# TeensyAmp_R4_1.net
KiCad netlist of a schematic drawn in EAGLE
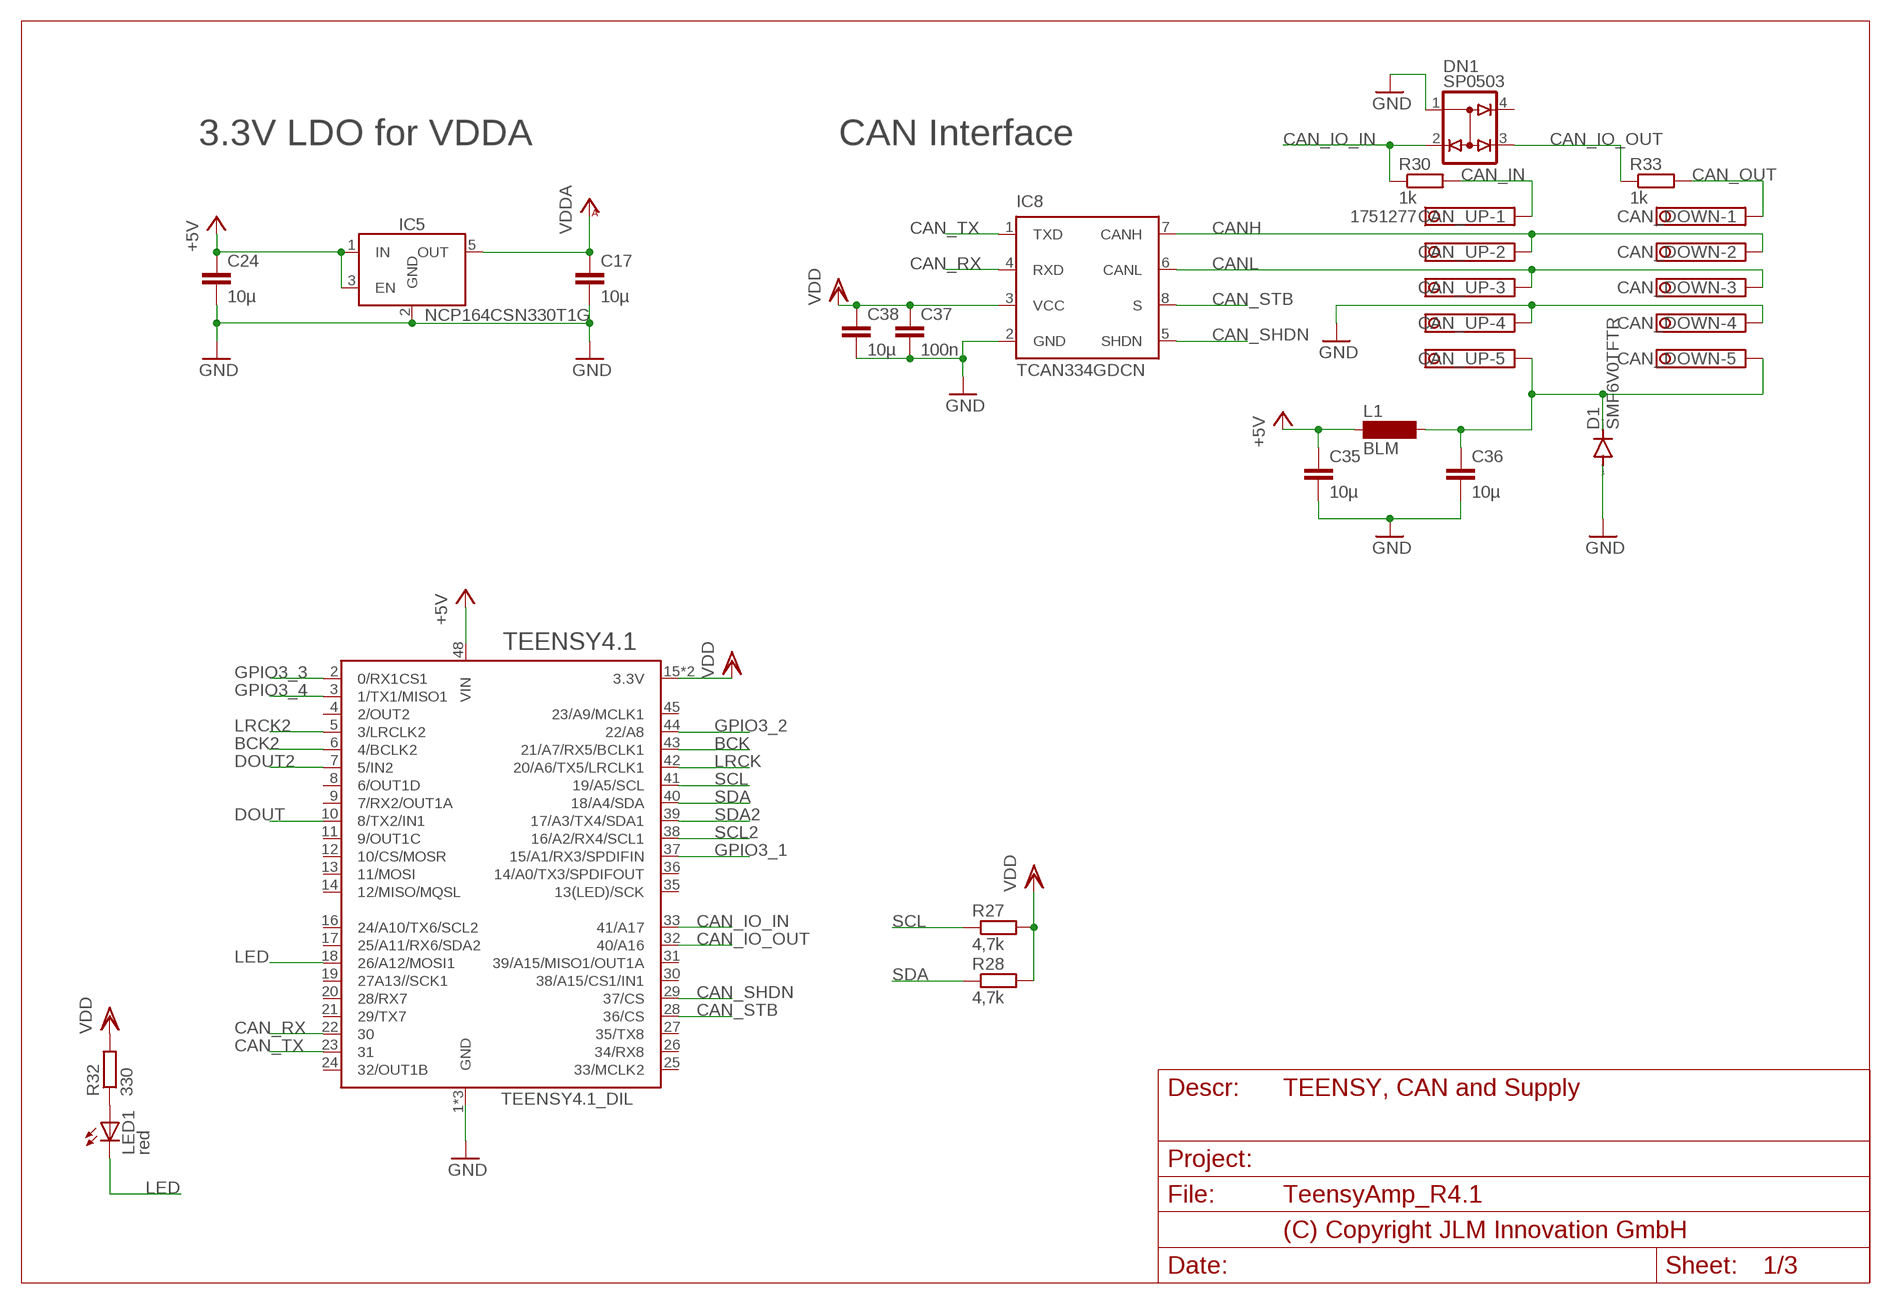
[diagram p0: schematic, sheet 1]
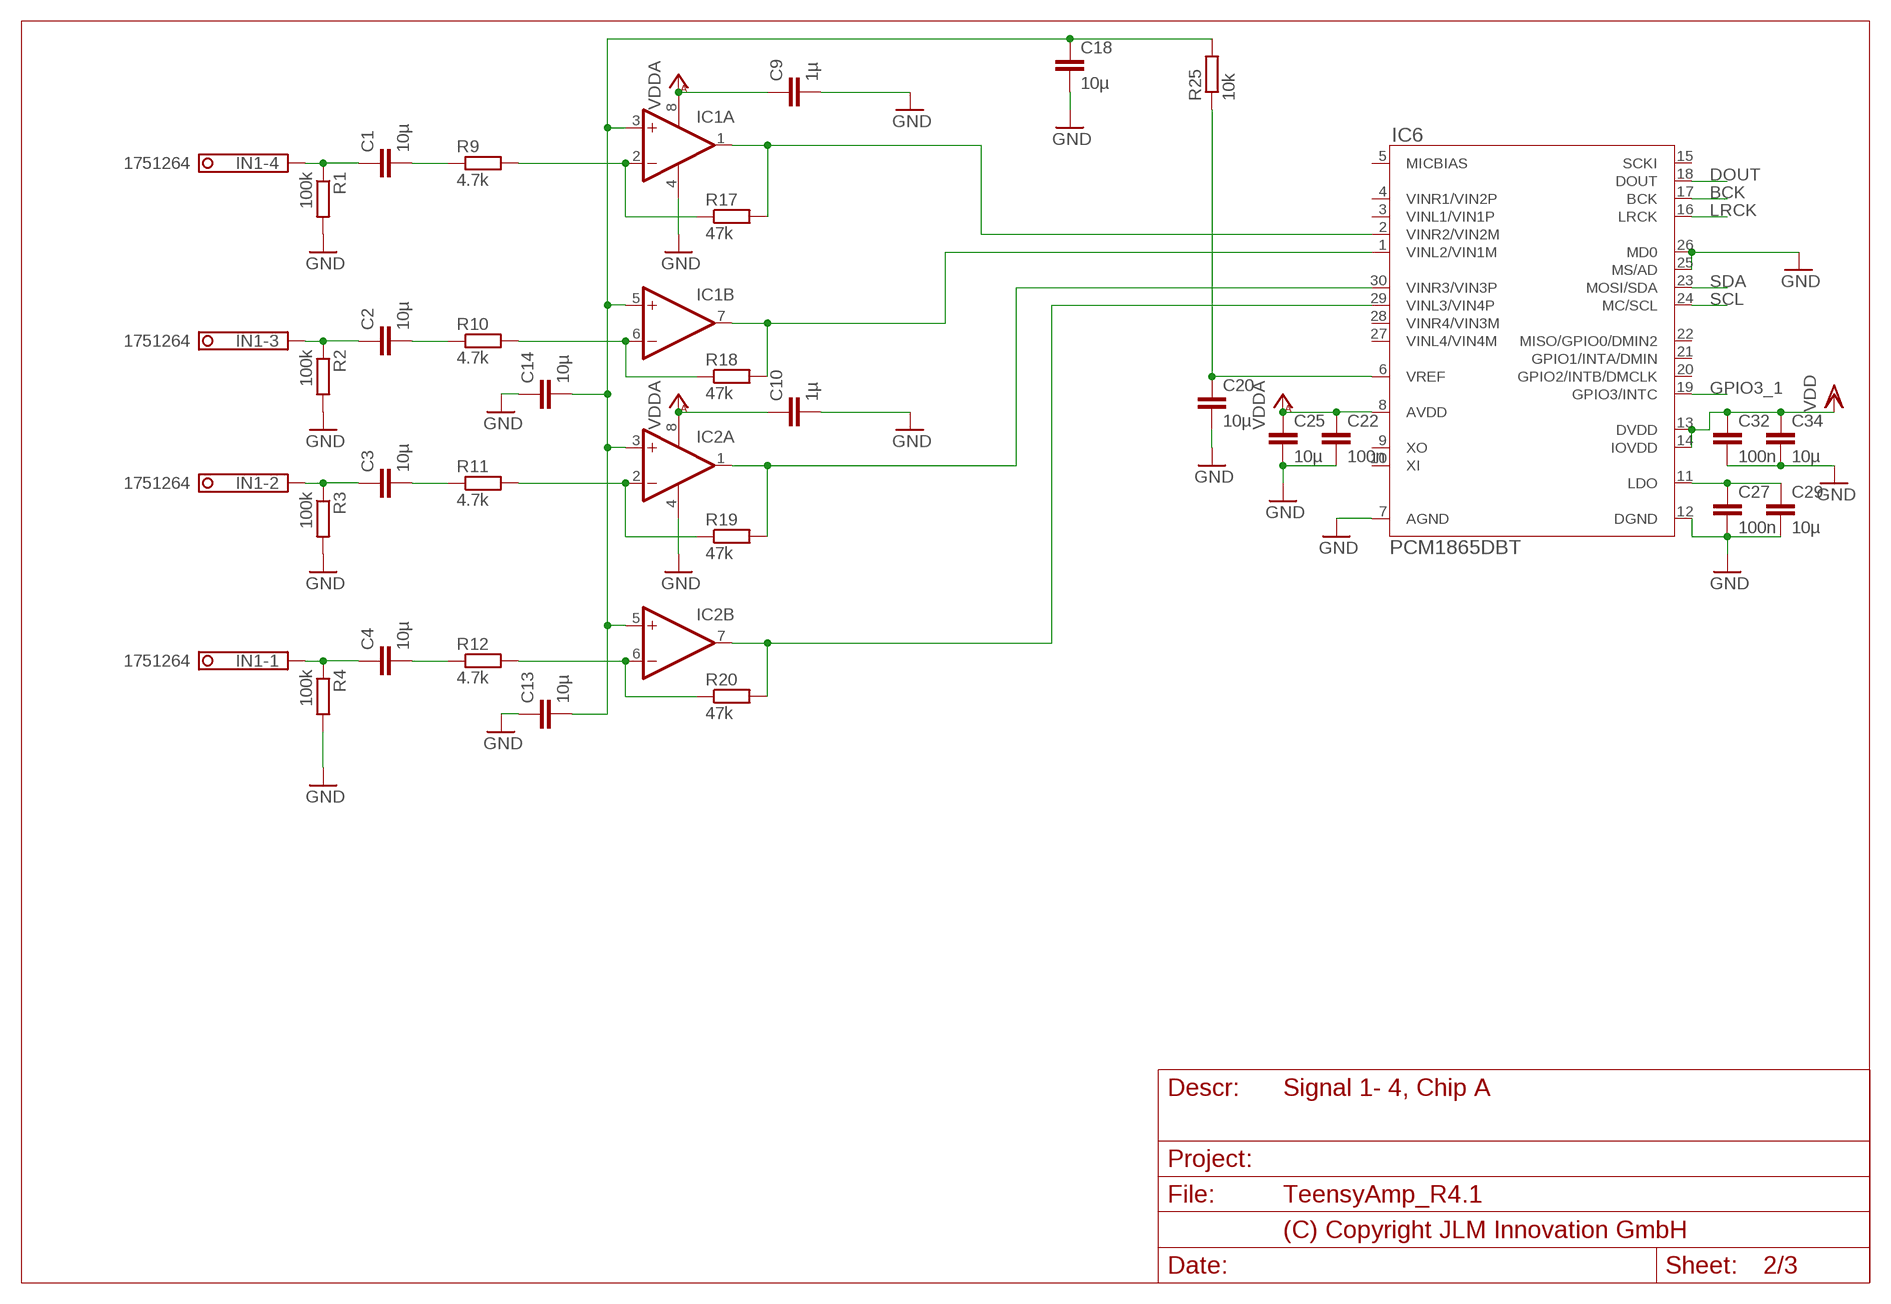
[diagram p1: schematic, sheet 2]
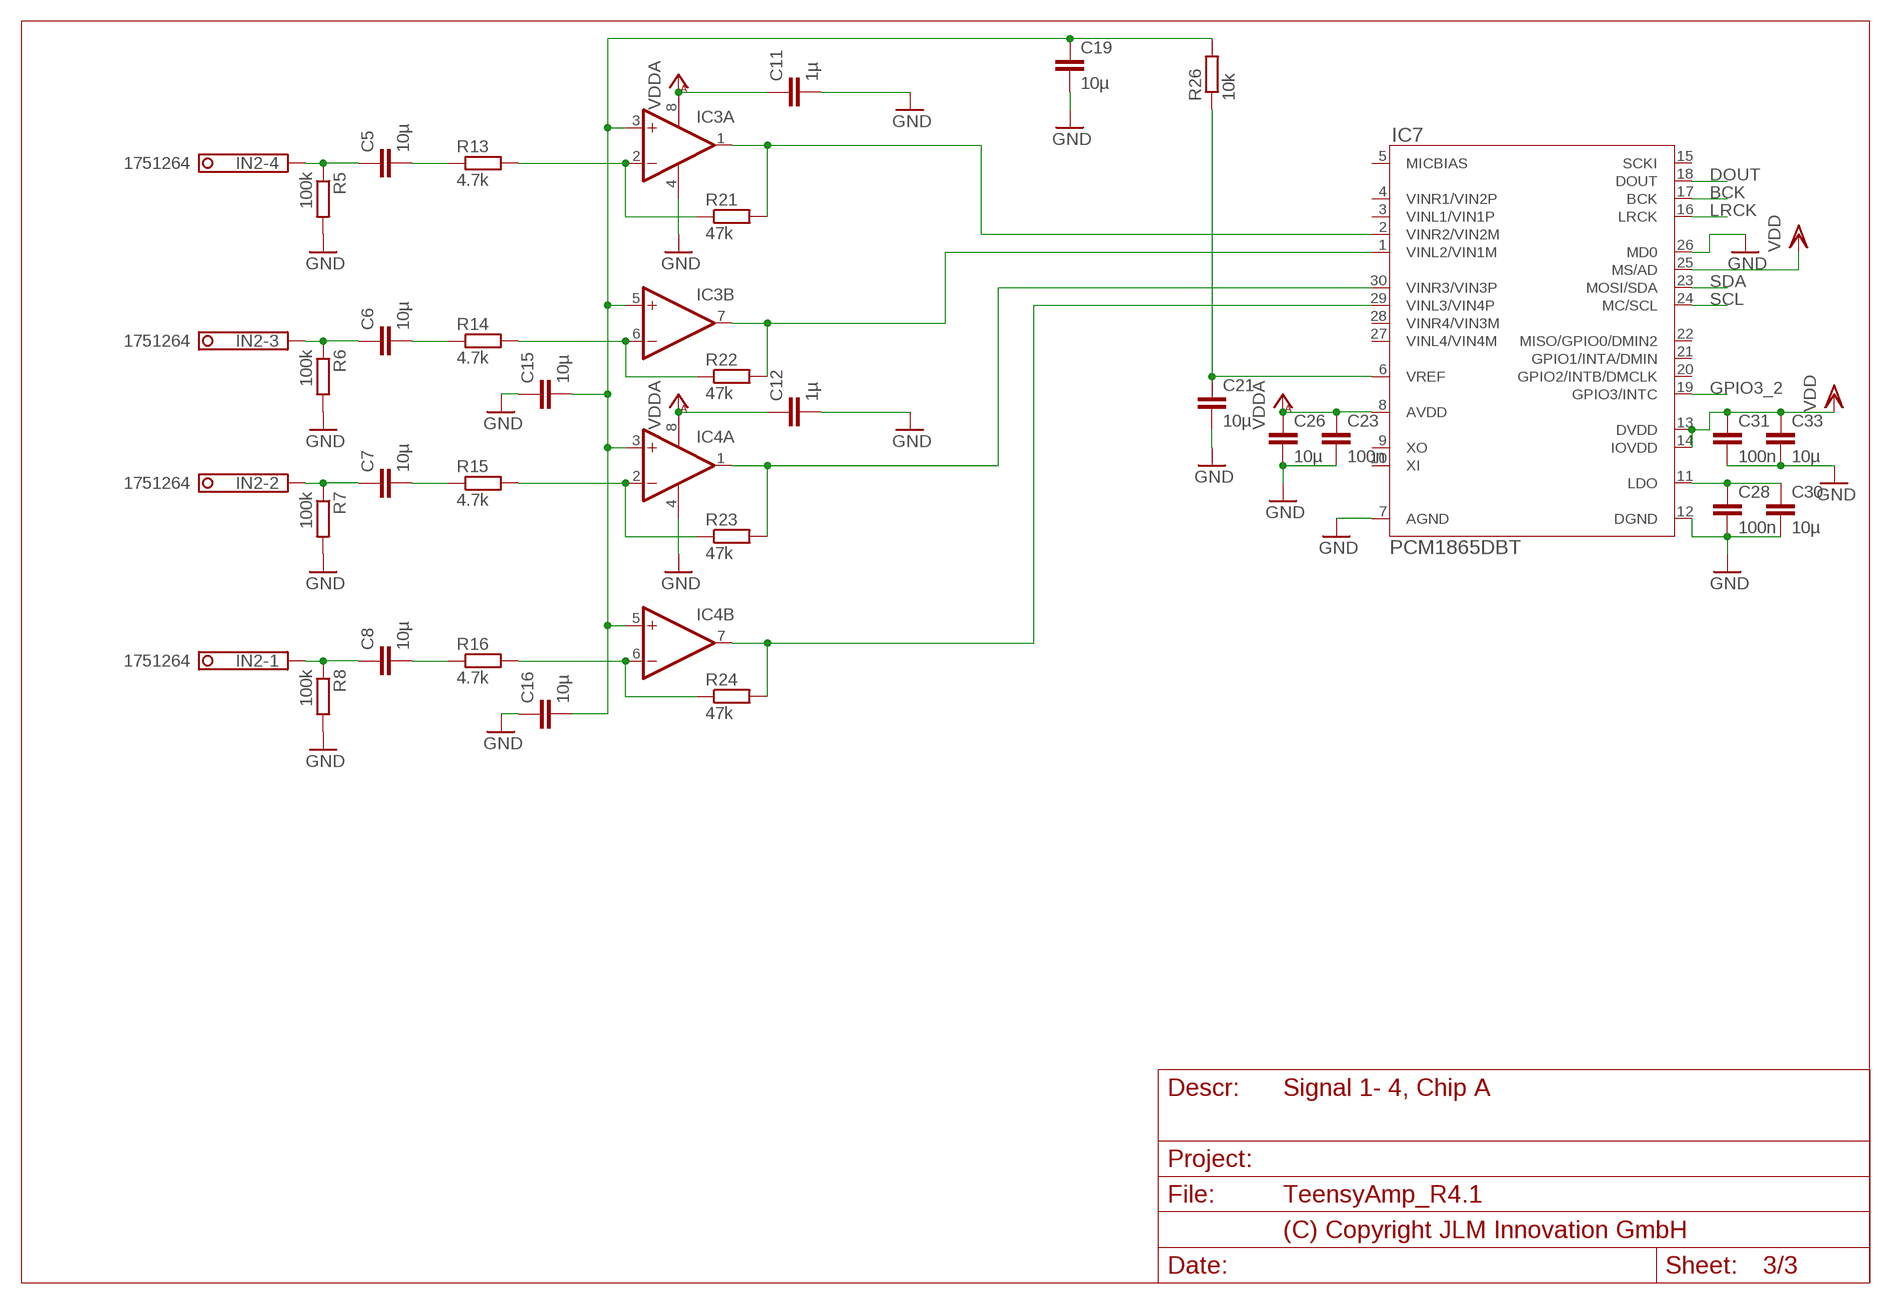
[diagram p2: schematic, sheet 3]

(export (version "E")
  (design (tool "Eeschema 10.0.6"))
  (components
    (comp (ref "C1")
      (value "10µ")
      (footprint "eagle-import:C0805")
      (libsource (lib "eagle-import") (part "C-EUC0805"))
    )
    (comp (ref "C2")
      (value "10µ")
      (footprint "eagle-import:C0805")
      (libsource (lib "eagle-import") (part "C-EUC0805"))
    )
    (comp (ref "C3")
      (value "10µ")
      (footprint "eagle-import:C0805")
      (libsource (lib "eagle-import") (part "C-EUC0805"))
    )
    (comp (ref "C4")
      (value "10µ")
      (footprint "eagle-import:C0805")
      (libsource (lib "eagle-import") (part "C-EUC0805"))
    )
    (comp (ref "C9")
      (value "1µ")
      (footprint "eagle-import:C0603")
      (libsource (lib "eagle-import") (part "C-EUC0603"))
    )
    (comp (ref "C10")
      (value "1µ")
      (footprint "eagle-import:C0603")
      (libsource (lib "eagle-import") (part "C-EUC0603"))
    )
    (comp (ref "C13")
      (value "10µ")
      (footprint "eagle-import:C0603")
      (libsource (lib "eagle-import") (part "C-EUC0603"))
    )
    (comp (ref "C14")
      (value "10µ")
      (footprint "eagle-import:C0603")
      (libsource (lib "eagle-import") (part "C-EUC0603"))
    )
    (comp (ref "C18")
      (value "10µ")
      (footprint "eagle-import:C0603")
      (libsource (lib "eagle-import") (part "C-EUC0603"))
    )
    (comp (ref "C20")
      (value "10µ")
      (footprint "eagle-import:C0603")
      (libsource (lib "eagle-import") (part "C-EUC0603"))
    )
    (comp (ref "C22")
      (value "100n")
      (footprint "eagle-import:C0603")
      (libsource (lib "eagle-import") (part "C-EUC0603"))
    )
    (comp (ref "C25")
      (value "10µ")
      (footprint "eagle-import:C0603")
      (libsource (lib "eagle-import") (part "C-EUC0603"))
    )
    (comp (ref "C27")
      (value "100n")
      (footprint "eagle-import:C0603")
      (libsource (lib "eagle-import") (part "C-EUC0603"))
    )
    (comp (ref "C29")
      (value "10µ")
      (footprint "eagle-import:C0603")
      (libsource (lib "eagle-import") (part "C-EUC0603"))
    )
    (comp (ref "C32")
      (value "100n")
      (footprint "eagle-import:C0603")
      (libsource (lib "eagle-import") (part "C-EUC0603"))
    )
    (comp (ref "C34")
      (value "10µ")
      (footprint "eagle-import:C0603")
      (libsource (lib "eagle-import") (part "C-EUC0603"))
    )
    (comp (ref "IC1")
      (value "OPA2344E")
      (footprint "eagle-import:MSOP08")
      (libsource (lib "eagle-import") (part "OPA2E344"))
    )
    (comp (ref "IC2")
      (value "OPA2344E")
      (footprint "eagle-import:MSOP08")
      (libsource (lib "eagle-import") (part "OPA2E344"))
    )
    (comp (ref "IC6")
      (value "PCM1865DBT")
      (footprint "eagle-import:SOP50P640X120-30N")
      (libsource (lib "eagle-import") (part "PCM1865DBT"))
    )
    (comp (ref "IN1")
      (value "1751264")
      (footprint "eagle-import:1751264")
      (fields (field (name "OC_FARNELL") "2478588"))
      (libsource (lib "eagle-import") (part "1751264"))
    )
    (comp (ref "R1")
      (value "100k")
      (footprint "eagle-import:R0603")
      (libsource (lib "eagle-import") (part "R_JLMR0603"))
    )
    (comp (ref "R2")
      (value "100k")
      (footprint "eagle-import:R0603")
      (libsource (lib "eagle-import") (part "R_JLMR0603"))
    )
    (comp (ref "R3")
      (value "100k")
      (footprint "eagle-import:R0603")
      (libsource (lib "eagle-import") (part "R_JLMR0603"))
    )
    (comp (ref "R4")
      (value "100k")
      (footprint "eagle-import:R0603")
      (libsource (lib "eagle-import") (part "R_JLMR0603"))
    )
    (comp (ref "R9")
      (value "4.7k")
      (footprint "eagle-import:R0603")
      (libsource (lib "eagle-import") (part "R_JLMR0603"))
    )
    (comp (ref "R10")
      (value "4.7k")
      (footprint "eagle-import:R0603")
      (libsource (lib "eagle-import") (part "R_JLMR0603"))
    )
    (comp (ref "R11")
      (value "4.7k")
      (footprint "eagle-import:R0603")
      (libsource (lib "eagle-import") (part "R_JLMR0603"))
    )
    (comp (ref "R12")
      (value "4.7k")
      (footprint "eagle-import:R0603")
      (libsource (lib "eagle-import") (part "R_JLMR0603"))
    )
    (comp (ref "R17")
      (value "47k")
      (footprint "eagle-import:R0603")
      (libsource (lib "eagle-import") (part "R_JLMR0603"))
    )
    (comp (ref "R18")
      (value "47k")
      (footprint "eagle-import:R0603")
      (libsource (lib "eagle-import") (part "R_JLMR0603"))
    )
    (comp (ref "R19")
      (value "47k")
      (footprint "eagle-import:R0603")
      (libsource (lib "eagle-import") (part "R_JLMR0603"))
    )
    (comp (ref "R20")
      (value "47k")
      (footprint "eagle-import:R0603")
      (libsource (lib "eagle-import") (part "R_JLMR0603"))
    )
    (comp (ref "R25")
      (value "10k")
      (footprint "eagle-import:R0603")
      (libsource (lib "eagle-import") (part "R_JLMR0603"))
    )
    (comp (ref "C17")
      (value "10µ")
      (footprint "eagle-import:C0603")
      (libsource (lib "eagle-import") (part "C-EUC0603"))
    )
    (comp (ref "C24")
      (value "10µ")
      (footprint "eagle-import:C0603")
      (libsource (lib "eagle-import") (part "C-EUC0603"))
    )
    (comp (ref "C35")
      (value "10µ")
      (footprint "eagle-import:C0805")
      (libsource (lib "eagle-import") (part "C-EUC0805"))
    )
    (comp (ref "C36")
      (value "10µ")
      (footprint "eagle-import:C0805")
      (libsource (lib "eagle-import") (part "C-EUC0805"))
    )
    (comp (ref "C37")
      (value "100n")
      (footprint "eagle-import:C0603")
      (libsource (lib "eagle-import") (part "C-EUC0603"))
    )
    (comp (ref "C38")
      (value "10µ")
      (footprint "eagle-import:C0603")
      (libsource (lib "eagle-import") (part "C-EUC0603"))
    )
    (comp (ref "CAN_DOWN")
      (value "1751277")
      (footprint "eagle-import:1751277")
      (fields (field (name "OC_RS") "8024855"))
      (libsource (lib "eagle-import") (part "1751277"))
    )
    (comp (ref "CAN_UP")
      (value "1751277")
      (footprint "eagle-import:1751277")
      (fields (field (name "OC_RS") "8024855"))
      (libsource (lib "eagle-import") (part "1751277"))
    )
    (comp (ref "D1")
      (value "SMF6V0TFTR")
      (footprint "eagle-import:SOD123")
      (libsource (lib "eagle-import") (part "DIODE-SOD123"))
    )
    (comp (ref "DN1")
      (value "SP0503")
      (footprint "eagle-import:SOT143-R")
      (fields (field (name "OC_FARNELL") "1827633"))
      (libsource (lib "eagle-import") (part "SP0503"))
    )
    (comp (ref "IC5")
      (value "NCP164CSN330T1G")
      (footprint "eagle-import:SOT23-5")
      (libsource (lib "eagle-import") (part "LDO_ENSOT23-5"))
    )
    (comp (ref "IC8")
      (value "TCAN334GDCN")
      (footprint "eagle-import:SOT65P280X145-8N")
      (libsource (lib "eagle-import") (part "TCAN330DCN"))
    )
    (comp (ref "L1")
      (value "BLM")
      (footprint "eagle-import:R0805")
      (libsource (lib "eagle-import") (part "L_JLM0805"))
    )
    (comp (ref "LED1")
      (value "red")
      (footprint "eagle-import:LED5MM")
      (libsource (lib "eagle-import") (part "LED5MM"))
    )
    (comp (ref "R27")
      (value "4,7k")
      (footprint "eagle-import:R0603")
      (libsource (lib "eagle-import") (part "R_JLMR0603"))
    )
    (comp (ref "R28")
      (value "4,7k")
      (footprint "eagle-import:R0603")
      (libsource (lib "eagle-import") (part "R_JLMR0603"))
    )
    (comp (ref "R30")
      (value "1k")
      (footprint "eagle-import:R0603")
      (libsource (lib "eagle-import") (part "R_JLMR0603"))
    )
    (comp (ref "R32")
      (value "330")
      (footprint "eagle-import:R0603")
      (libsource (lib "eagle-import") (part "R_JLMR0603"))
    )
    (comp (ref "R33")
      (value "1k")
      (footprint "eagle-import:R0603")
      (libsource (lib "eagle-import") (part "R_JLMR0603"))
    )
    (comp (ref "TEENSY4.1")
      (value "TEENSY4.1_DIL")
      (footprint "eagle-import:TEENSY4.1_DIL")
      (libsource (lib "eagle-import") (part "TEENSY4.1_DIL"))
    )
    (comp (ref "C5")
      (value "10µ")
      (footprint "eagle-import:C0805")
      (libsource (lib "eagle-import") (part "C-EUC0805"))
    )
    (comp (ref "C6")
      (value "10µ")
      (footprint "eagle-import:C0805")
      (libsource (lib "eagle-import") (part "C-EUC0805"))
    )
    (comp (ref "C7")
      (value "10µ")
      (footprint "eagle-import:C0805")
      (libsource (lib "eagle-import") (part "C-EUC0805"))
    )
    (comp (ref "C8")
      (value "10µ")
      (footprint "eagle-import:C0805")
      (libsource (lib "eagle-import") (part "C-EUC0805"))
    )
    (comp (ref "C11")
      (value "1µ")
      (footprint "eagle-import:C0603")
      (libsource (lib "eagle-import") (part "C-EUC0603"))
    )
    (comp (ref "C12")
      (value "1µ")
      (footprint "eagle-import:C0603")
      (libsource (lib "eagle-import") (part "C-EUC0603"))
    )
    (comp (ref "C15")
      (value "10µ")
      (footprint "eagle-import:C0603")
      (libsource (lib "eagle-import") (part "C-EUC0603"))
    )
    (comp (ref "C16")
      (value "10µ")
      (footprint "eagle-import:C0603")
      (libsource (lib "eagle-import") (part "C-EUC0603"))
    )
    (comp (ref "C19")
      (value "10µ")
      (footprint "eagle-import:C0603")
      (libsource (lib "eagle-import") (part "C-EUC0603"))
    )
    (comp (ref "C21")
      (value "10µ")
      (footprint "eagle-import:C0603")
      (libsource (lib "eagle-import") (part "C-EUC0603"))
    )
    (comp (ref "C23")
      (value "100n")
      (footprint "eagle-import:C0603")
      (libsource (lib "eagle-import") (part "C-EUC0603"))
    )
    (comp (ref "C26")
      (value "10µ")
      (footprint "eagle-import:C0603")
      (libsource (lib "eagle-import") (part "C-EUC0603"))
    )
    (comp (ref "C28")
      (value "100n")
      (footprint "eagle-import:C0603")
      (libsource (lib "eagle-import") (part "C-EUC0603"))
    )
    (comp (ref "C30")
      (value "10µ")
      (footprint "eagle-import:C0603")
      (libsource (lib "eagle-import") (part "C-EUC0603"))
    )
    (comp (ref "C31")
      (value "100n")
      (footprint "eagle-import:C0603")
      (libsource (lib "eagle-import") (part "C-EUC0603"))
    )
    (comp (ref "C33")
      (value "10µ")
      (footprint "eagle-import:C0603")
      (libsource (lib "eagle-import") (part "C-EUC0603"))
    )
    (comp (ref "IC3")
      (value "OPA2344E")
      (footprint "eagle-import:MSOP08")
      (libsource (lib "eagle-import") (part "OPA2E344"))
    )
    (comp (ref "IC4")
      (value "OPA2344E")
      (footprint "eagle-import:MSOP08")
      (libsource (lib "eagle-import") (part "OPA2E344"))
    )
    (comp (ref "IC7")
      (value "PCM1865DBT")
      (footprint "eagle-import:SOP50P640X120-30N")
      (libsource (lib "eagle-import") (part "PCM1865DBT"))
    )
    (comp (ref "IN2")
      (value "1751264")
      (footprint "eagle-import:1751264")
      (fields (field (name "OC_FARNELL") "2478588") (field (name "OC_RS") "8024852"))
      (libsource (lib "eagle-import") (part "1751264"))
    )
    (comp (ref "R5")
      (value "100k")
      (footprint "eagle-import:R0603")
      (libsource (lib "eagle-import") (part "R_JLMR0603"))
    )
    (comp (ref "R6")
      (value "100k")
      (footprint "eagle-import:R0603")
      (libsource (lib "eagle-import") (part "R_JLMR0603"))
    )
    (comp (ref "R7")
      (value "100k")
      (footprint "eagle-import:R0603")
      (libsource (lib "eagle-import") (part "R_JLMR0603"))
    )
    (comp (ref "R8")
      (value "100k")
      (footprint "eagle-import:R0603")
      (libsource (lib "eagle-import") (part "R_JLMR0603"))
    )
    (comp (ref "R13")
      (value "4.7k")
      (footprint "eagle-import:R0603")
      (libsource (lib "eagle-import") (part "R_JLMR0603"))
    )
    (comp (ref "R14")
      (value "4.7k")
      (footprint "eagle-import:R0603")
      (libsource (lib "eagle-import") (part "R_JLMR0603"))
    )
    (comp (ref "R15")
      (value "4.7k")
      (footprint "eagle-import:R0603")
      (libsource (lib "eagle-import") (part "R_JLMR0603"))
    )
    (comp (ref "R16")
      (value "4.7k")
      (footprint "eagle-import:R0603")
      (libsource (lib "eagle-import") (part "R_JLMR0603"))
    )
    (comp (ref "R21")
      (value "47k")
      (footprint "eagle-import:R0603")
      (libsource (lib "eagle-import") (part "R_JLMR0603"))
    )
    (comp (ref "R22")
      (value "47k")
      (footprint "eagle-import:R0603")
      (libsource (lib "eagle-import") (part "R_JLMR0603"))
    )
    (comp (ref "R23")
      (value "47k")
      (footprint "eagle-import:R0603")
      (libsource (lib "eagle-import") (part "R_JLMR0603"))
    )
    (comp (ref "R24")
      (value "47k")
      (footprint "eagle-import:R0603")
      (libsource (lib "eagle-import") (part "R_JLMR0603"))
    )
    (comp (ref "R26")
      (value "10k")
      (footprint "eagle-import:R0603")
      (libsource (lib "eagle-import") (part "R_JLMR0603"))
    )
  )
  (nets
    (net (code "1") (name "+5V") (class "Default")
      (node (ref "C24") (pin "1") (pinfunction "1_1") (pintype "passive"))
      (node (ref "C35") (pin "1") (pinfunction "1_1") (pintype "passive"))
      (node (ref "IC5") (pin "1") (pinfunction "IN_1") (pintype "input"))
      (node (ref "IC5") (pin "3") (pinfunction "EN_3") (pintype "input"))
      (node (ref "L1") (pin "1") (pinfunction "1_1") (pintype "passive"))
      (node (ref "TEENSY4.1") (pin "48") (pinfunction "VIN_48") (pintype "power_in"))
    )
    (net (code "2") (name "BCK") (class "Default")
      (node (ref "IC6") (pin "17") (pinfunction "BCK_17") (pintype "bidirectional"))
      (node (ref "IC7") (pin "17") (pinfunction "BCK_17") (pintype "bidirectional"))
      (node (ref "TEENSY4.1") (pin "43") (pinfunction "21/A7/RX5/BCLK1_43") (pintype "bidirectional"))
    )
    (net (code "3") (name "BCK2") (class "Default")
      (node (ref "TEENSY4.1") (pin "6") (pinfunction "4/BCLK2_6") (pintype "bidirectional"))
    )
    (net (code "4") (name "CANH") (class "Default")
      (node (ref "CAN_DOWN") (pin "2") (pinfunction "K_2") (pintype "passive"))
      (node (ref "CAN_UP") (pin "2") (pinfunction "K_2") (pintype "passive"))
      (node (ref "IC8") (pin "7") (pinfunction "CANH_7") (pintype "passive"))
    )
    (net (code "5") (name "CANL") (class "Default")
      (node (ref "CAN_DOWN") (pin "3") (pinfunction "K_3") (pintype "passive"))
      (node (ref "CAN_UP") (pin "3") (pinfunction "K_3") (pintype "passive"))
      (node (ref "IC8") (pin "6") (pinfunction "CANL_6") (pintype "passive"))
    )
    (net (code "6") (name "CAN_IN") (class "Default")
      (node (ref "CAN_UP") (pin "1") (pinfunction "K_1") (pintype "passive"))
      (node (ref "R30") (pin "2") (pinfunction "2_2") (pintype "passive"))
    )
    (net (code "7") (name "CAN_IO_IN") (class "Default")
      (node (ref "DN1") (pin "2") (pinfunction "C2_2") (pintype "passive"))
      (node (ref "R30") (pin "1") (pinfunction "1_1") (pintype "passive"))
      (node (ref "TEENSY4.1") (pin "33") (pinfunction "41/A17_33") (pintype "bidirectional"))
    )
    (net (code "8") (name "CAN_IO_OUT") (class "Default")
      (node (ref "DN1") (pin "3") (pinfunction "C3_3") (pintype "passive"))
      (node (ref "R33") (pin "1") (pinfunction "1_1") (pintype "passive"))
      (node (ref "TEENSY4.1") (pin "32") (pinfunction "40/A16_32") (pintype "bidirectional"))
    )
    (net (code "9") (name "CAN_OUT") (class "Default")
      (node (ref "CAN_DOWN") (pin "1") (pinfunction "K_1") (pintype "passive"))
      (node (ref "R33") (pin "2") (pinfunction "2_2") (pintype "passive"))
    )
    (net (code "10") (name "CAN_RX") (class "Default")
      (node (ref "IC8") (pin "4") (pinfunction "RXD_4") (pintype "output"))
      (node (ref "TEENSY4.1") (pin "22") (pinfunction "30_22") (pintype "bidirectional"))
    )
    (net (code "11") (name "CAN_SHDN") (class "Default")
      (node (ref "IC8") (pin "5") (pinfunction "SHDN_5") (pintype "input"))
      (node (ref "TEENSY4.1") (pin "29") (pinfunction "37/CS_29") (pintype "bidirectional"))
    )
    (net (code "12") (name "CAN_STB") (class "Default")
      (node (ref "IC8") (pin "8") (pinfunction "S_8") (pintype "input"))
      (node (ref "TEENSY4.1") (pin "28") (pinfunction "36/CS_28") (pintype "bidirectional"))
    )
    (net (code "13") (name "CAN_TX") (class "Default")
      (node (ref "IC8") (pin "1") (pinfunction "TXD_1") (pintype "input"))
      (node (ref "TEENSY4.1") (pin "23") (pinfunction "31_23") (pintype "bidirectional"))
    )
    (net (code "14") (name "DOUT") (class "Default")
      (node (ref "IC6") (pin "18") (pinfunction "DOUT_18") (pintype "output"))
      (node (ref "IC7") (pin "18") (pinfunction "DOUT_18") (pintype "output"))
      (node (ref "TEENSY4.1") (pin "10") (pinfunction "8/TX2/IN1_10") (pintype "bidirectional"))
    )
    (net (code "15") (name "DOUT2") (class "Default")
      (node (ref "TEENSY4.1") (pin "7") (pinfunction "5/IN2_7") (pintype "bidirectional"))
    )
    (net (code "16") (name "GND") (class "Default")
      (node (ref "C10") (pin "2") (pinfunction "2_2") (pintype "passive"))
      (node (ref "C11") (pin "2") (pinfunction "2_2") (pintype "passive"))
      (node (ref "C12") (pin "2") (pinfunction "2_2") (pintype "passive"))
      (node (ref "C13") (pin "1") (pinfunction "1_1") (pintype "passive"))
      (node (ref "C14") (pin "1") (pinfunction "1_1") (pintype "passive"))
      (node (ref "C15") (pin "1") (pinfunction "1_1") (pintype "passive"))
      (node (ref "C16") (pin "1") (pinfunction "1_1") (pintype "passive"))
      (node (ref "C17") (pin "2") (pinfunction "2_2") (pintype "passive"))
      (node (ref "C18") (pin "2") (pinfunction "2_2") (pintype "passive"))
      (node (ref "C19") (pin "2") (pinfunction "2_2") (pintype "passive"))
      (node (ref "C20") (pin "2") (pinfunction "2_2") (pintype "passive"))
      (node (ref "C21") (pin "2") (pinfunction "2_2") (pintype "passive"))
      (node (ref "C22") (pin "2") (pinfunction "2_2") (pintype "passive"))
      (node (ref "C23") (pin "2") (pinfunction "2_2") (pintype "passive"))
      (node (ref "C24") (pin "2") (pinfunction "2_2") (pintype "passive"))
      (node (ref "C25") (pin "2") (pinfunction "2_2") (pintype "passive"))
      (node (ref "C26") (pin "2") (pinfunction "2_2") (pintype "passive"))
      (node (ref "C27") (pin "2") (pinfunction "2_2") (pintype "passive"))
      (node (ref "C28") (pin "2") (pinfunction "2_2") (pintype "passive"))
      (node (ref "C29") (pin "2") (pinfunction "2_2") (pintype "passive"))
      (node (ref "C30") (pin "2") (pinfunction "2_2") (pintype "passive"))
      (node (ref "C31") (pin "2") (pinfunction "2_2") (pintype "passive"))
      (node (ref "C32") (pin "2") (pinfunction "2_2") (pintype "passive"))
      (node (ref "C33") (pin "2") (pinfunction "2_2") (pintype "passive"))
      (node (ref "C34") (pin "2") (pinfunction "2_2") (pintype "passive"))
      (node (ref "C35") (pin "2") (pinfunction "2_2") (pintype "passive"))
      (node (ref "C36") (pin "2") (pinfunction "2_2") (pintype "passive"))
      (node (ref "C37") (pin "2") (pinfunction "2_2") (pintype "passive"))
      (node (ref "C38") (pin "2") (pinfunction "2_2") (pintype "passive"))
      (node (ref "C9") (pin "2") (pinfunction "2_2") (pintype "passive"))
      (node (ref "CAN_DOWN") (pin "4") (pinfunction "K_4") (pintype "passive"))
      (node (ref "CAN_UP") (pin "4") (pinfunction "K_4") (pintype "passive"))
      (node (ref "D1") (pin "A") (pinfunction "A_A") (pintype "passive"))
      (node (ref "DN1") (pin "1") (pinfunction "A1_1") (pintype "passive"))
      (node (ref "IC1") (pin "4") (pinfunction "V-_4") (pintype "power_in"))
      (node (ref "IC2") (pin "4") (pinfunction "V-_4") (pintype "power_in"))
      (node (ref "IC3") (pin "4") (pinfunction "V-_4") (pintype "power_in"))
      (node (ref "IC4") (pin "4") (pinfunction "V-_4") (pintype "power_in"))
      (node (ref "IC5") (pin "2") (pinfunction "GND_2") (pintype "power_in"))
      (node (ref "IC6") (pin "12") (pinfunction "DGND_12") (pintype "power_in"))
      (node (ref "IC6") (pin "25") (pinfunction "MS/AD_25") (pintype "input"))
      (node (ref "IC6") (pin "26") (pinfunction "MD0_26") (pintype "input"))
      (node (ref "IC6") (pin "7") (pinfunction "AGND_7") (pintype "power_in"))
      (node (ref "IC7") (pin "12") (pinfunction "DGND_12") (pintype "power_in"))
      (node (ref "IC7") (pin "26") (pinfunction "MD0_26") (pintype "input"))
      (node (ref "IC7") (pin "7") (pinfunction "AGND_7") (pintype "power_in"))
      (node (ref "IC8") (pin "2") (pinfunction "GND_2") (pintype "power_in"))
      (node (ref "R1") (pin "2") (pinfunction "2_2") (pintype "passive"))
      (node (ref "R2") (pin "2") (pinfunction "2_2") (pintype "passive"))
      (node (ref "R3") (pin "2") (pinfunction "2_2") (pintype "passive"))
      (node (ref "R4") (pin "2") (pinfunction "2_2") (pintype "passive"))
      (node (ref "R5") (pin "2") (pinfunction "2_2") (pintype "passive"))
      (node (ref "R6") (pin "2") (pinfunction "2_2") (pintype "passive"))
      (node (ref "R7") (pin "2") (pinfunction "2_2") (pintype "passive"))
      (node (ref "R8") (pin "2") (pinfunction "2_2") (pintype "passive"))
      (node (ref "TEENSY4.1") (pin "1") (pinfunction "GND_1") (pintype "power_in"))
      (node (ref "TEENSY4.1") (pin "34") (pinfunction "GND_34") (pintype "power_in"))
      (node (ref "TEENSY4.1") (pin "47") (pinfunction "GND_47") (pintype "power_in"))
    )
    (net (code "17") (name "GPIO3_1") (class "Default")
      (node (ref "IC6") (pin "19") (pinfunction "GPIO3/INTC_19") (pintype "bidirectional"))
      (node (ref "TEENSY4.1") (pin "37") (pinfunction "15/A1/RX3/SPDIFIN_37") (pintype "bidirectional"))
    )
    (net (code "18") (name "GPIO3_2") (class "Default")
      (node (ref "IC7") (pin "19") (pinfunction "GPIO3/INTC_19") (pintype "bidirectional"))
      (node (ref "TEENSY4.1") (pin "44") (pinfunction "22/A8_44") (pintype "bidirectional"))
    )
    (net (code "19") (name "GPIO3_3") (class "Default")
      (node (ref "TEENSY4.1") (pin "2") (pinfunction "0/RX1CS1_2") (pintype "bidirectional"))
    )
    (net (code "20") (name "GPIO3_4") (class "Default")
      (node (ref "TEENSY4.1") (pin "3") (pinfunction "1/TX1/MISO1_3") (pintype "bidirectional"))
    )
    (net (code "21") (name "LED") (class "Default")
      (node (ref "LED1") (pin "K") (pinfunction "C_K") (pintype "passive"))
      (node (ref "TEENSY4.1") (pin "18") (pinfunction "26/A12/MOSI1_18") (pintype "bidirectional"))
    )
    (net (code "22") (name "LRCK") (class "Default")
      (node (ref "IC6") (pin "16") (pinfunction "LRCK_16") (pintype "bidirectional"))
      (node (ref "IC7") (pin "16") (pinfunction "LRCK_16") (pintype "bidirectional"))
      (node (ref "TEENSY4.1") (pin "42") (pinfunction "20/A6/TX5/LRCLK1_42") (pintype "bidirectional"))
    )
    (net (code "23") (name "LRCK2") (class "Default")
      (node (ref "TEENSY4.1") (pin "5") (pinfunction "3/LRCLK2_5") (pintype "bidirectional"))
    )
    (net (code "24") (name "Net-(C1-Pad2)") (class "Default")
      (node (ref "C1") (pin "2") (pinfunction "2_2") (pintype "passive"))
      (node (ref "R9") (pin "1") (pinfunction "1_1") (pintype "passive"))
    )
    (net (code "25") (name "Net-(C2-Pad2)") (class "Default")
      (node (ref "C2") (pin "2") (pinfunction "2_2") (pintype "passive"))
      (node (ref "R10") (pin "1") (pinfunction "1_1") (pintype "passive"))
    )
    (net (code "26") (name "Net-(C3-Pad2)") (class "Default")
      (node (ref "C3") (pin "2") (pinfunction "2_2") (pintype "passive"))
      (node (ref "R11") (pin "1") (pinfunction "1_1") (pintype "passive"))
    )
    (net (code "27") (name "Net-(C4-Pad2)") (class "Default")
      (node (ref "C4") (pin "2") (pinfunction "2_2") (pintype "passive"))
      (node (ref "R12") (pin "1") (pinfunction "1_1") (pintype "passive"))
    )
    (net (code "28") (name "Net-(C5-Pad2)") (class "Default")
      (node (ref "C5") (pin "2") (pinfunction "2_2") (pintype "passive"))
      (node (ref "R13") (pin "1") (pinfunction "1_1") (pintype "passive"))
    )
    (net (code "29") (name "Net-(C6-Pad2)") (class "Default")
      (node (ref "C6") (pin "2") (pinfunction "2_2") (pintype "passive"))
      (node (ref "R14") (pin "1") (pinfunction "1_1") (pintype "passive"))
    )
    (net (code "30") (name "Net-(C7-Pad2)") (class "Default")
      (node (ref "C7") (pin "2") (pinfunction "2_2") (pintype "passive"))
      (node (ref "R15") (pin "1") (pinfunction "1_1") (pintype "passive"))
    )
    (net (code "31") (name "Net-(C8-Pad2)") (class "Default")
      (node (ref "C8") (pin "2") (pinfunction "2_2") (pintype "passive"))
      (node (ref "R16") (pin "1") (pinfunction "1_1") (pintype "passive"))
    )
    (net (code "32") (name "Net-(CAN_DOWNE-K)") (class "Default")
      (node (ref "C36") (pin "1") (pinfunction "1_1") (pintype "passive"))
      (node (ref "CAN_DOWN") (pin "5") (pinfunction "K_5") (pintype "passive"))
      (node (ref "CAN_UP") (pin "5") (pinfunction "K_5") (pintype "passive"))
      (node (ref "D1") (pin "C") (pinfunction "C_C") (pintype "passive"))
      (node (ref "L1") (pin "2") (pinfunction "2_2") (pintype "passive"))
    )
    (net (code "33") (name "Net-(IC1A-+IN)") (class "Default")
      (node (ref "C13") (pin "2") (pinfunction "2_2") (pintype "passive"))
      (node (ref "C14") (pin "2") (pinfunction "2_2") (pintype "passive"))
      (node (ref "C18") (pin "1") (pinfunction "1_1") (pintype "passive"))
      (node (ref "IC1") (pin "3") (pinfunction "+IN_3") (pintype "input"))
      (node (ref "IC1") (pin "5") (pinfunction "+IN_5") (pintype "input"))
      (node (ref "IC2") (pin "3") (pinfunction "+IN_3") (pintype "input"))
      (node (ref "IC2") (pin "5") (pinfunction "+IN_5") (pintype "input"))
      (node (ref "R25") (pin "2") (pinfunction "2_2") (pintype "passive"))
    )
    (net (code "34") (name "Net-(IC1A--IN)") (class "Default")
      (node (ref "IC1") (pin "2") (pinfunction "-IN_2") (pintype "input"))
      (node (ref "R17") (pin "1") (pinfunction "1_1") (pintype "passive"))
      (node (ref "R9") (pin "2") (pinfunction "2_2") (pintype "passive"))
    )
    (net (code "35") (name "Net-(IC1A-OUT)") (class "Default")
      (node (ref "IC1") (pin "1") (pinfunction "OUT_1") (pintype "output"))
      (node (ref "IC6") (pin "2") (pinfunction "VINR2/VIN2M_2") (pintype "input"))
      (node (ref "R17") (pin "2") (pinfunction "2_2") (pintype "passive"))
    )
    (net (code "36") (name "Net-(IC1B--IN)") (class "Default")
      (node (ref "IC1") (pin "6") (pinfunction "-IN_6") (pintype "input"))
      (node (ref "R10") (pin "2") (pinfunction "2_2") (pintype "passive"))
      (node (ref "R18") (pin "1") (pinfunction "1_1") (pintype "passive"))
    )
    (net (code "37") (name "Net-(IC1B-OUT)") (class "Default")
      (node (ref "IC1") (pin "7") (pinfunction "OUT_7") (pintype "output"))
      (node (ref "IC6") (pin "1") (pinfunction "VINL2/VIN1M_1") (pintype "input"))
      (node (ref "R18") (pin "2") (pinfunction "2_2") (pintype "passive"))
    )
    (net (code "38") (name "Net-(IC2A--IN)") (class "Default")
      (node (ref "IC2") (pin "2") (pinfunction "-IN_2") (pintype "input"))
      (node (ref "R11") (pin "2") (pinfunction "2_2") (pintype "passive"))
      (node (ref "R19") (pin "1") (pinfunction "1_1") (pintype "passive"))
    )
    (net (code "39") (name "Net-(IC2A-OUT)") (class "Default")
      (node (ref "IC2") (pin "1") (pinfunction "OUT_1") (pintype "output"))
      (node (ref "IC6") (pin "30") (pinfunction "VINR3/VIN3P_30") (pintype "input"))
      (node (ref "R19") (pin "2") (pinfunction "2_2") (pintype "passive"))
    )
    (net (code "40") (name "Net-(IC2B--IN)") (class "Default")
      (node (ref "IC2") (pin "6") (pinfunction "-IN_6") (pintype "input"))
      (node (ref "R12") (pin "2") (pinfunction "2_2") (pintype "passive"))
      (node (ref "R20") (pin "1") (pinfunction "1_1") (pintype "passive"))
    )
    (net (code "41") (name "Net-(IC2B-OUT)") (class "Default")
      (node (ref "IC2") (pin "7") (pinfunction "OUT_7") (pintype "output"))
      (node (ref "IC6") (pin "29") (pinfunction "VINL3/VIN4P_29") (pintype "input"))
      (node (ref "R20") (pin "2") (pinfunction "2_2") (pintype "passive"))
    )
    (net (code "42") (name "Net-(IC3A-+IN)") (class "Default")
      (node (ref "C15") (pin "2") (pinfunction "2_2") (pintype "passive"))
      (node (ref "C16") (pin "2") (pinfunction "2_2") (pintype "passive"))
      (node (ref "C19") (pin "1") (pinfunction "1_1") (pintype "passive"))
      (node (ref "IC3") (pin "3") (pinfunction "+IN_3") (pintype "input"))
      (node (ref "IC3") (pin "5") (pinfunction "+IN_5") (pintype "input"))
      (node (ref "IC4") (pin "3") (pinfunction "+IN_3") (pintype "input"))
      (node (ref "IC4") (pin "5") (pinfunction "+IN_5") (pintype "input"))
      (node (ref "R26") (pin "2") (pinfunction "2_2") (pintype "passive"))
    )
    (net (code "43") (name "Net-(IC3A--IN)") (class "Default")
      (node (ref "IC3") (pin "2") (pinfunction "-IN_2") (pintype "input"))
      (node (ref "R13") (pin "2") (pinfunction "2_2") (pintype "passive"))
      (node (ref "R21") (pin "1") (pinfunction "1_1") (pintype "passive"))
    )
    (net (code "44") (name "Net-(IC3A-OUT)") (class "Default")
      (node (ref "IC3") (pin "1") (pinfunction "OUT_1") (pintype "output"))
      (node (ref "IC7") (pin "2") (pinfunction "VINR2/VIN2M_2") (pintype "input"))
      (node (ref "R21") (pin "2") (pinfunction "2_2") (pintype "passive"))
    )
    (net (code "45") (name "Net-(IC3B--IN)") (class "Default")
      (node (ref "IC3") (pin "6") (pinfunction "-IN_6") (pintype "input"))
      (node (ref "R14") (pin "2") (pinfunction "2_2") (pintype "passive"))
      (node (ref "R22") (pin "1") (pinfunction "1_1") (pintype "passive"))
    )
    (net (code "46") (name "Net-(IC3B-OUT)") (class "Default")
      (node (ref "IC3") (pin "7") (pinfunction "OUT_7") (pintype "output"))
      (node (ref "IC7") (pin "1") (pinfunction "VINL2/VIN1M_1") (pintype "input"))
      (node (ref "R22") (pin "2") (pinfunction "2_2") (pintype "passive"))
    )
    (net (code "47") (name "Net-(IC4A--IN)") (class "Default")
      (node (ref "IC4") (pin "2") (pinfunction "-IN_2") (pintype "input"))
      (node (ref "R15") (pin "2") (pinfunction "2_2") (pintype "passive"))
      (node (ref "R23") (pin "1") (pinfunction "1_1") (pintype "passive"))
    )
    (net (code "48") (name "Net-(IC4A-OUT)") (class "Default")
      (node (ref "IC4") (pin "1") (pinfunction "OUT_1") (pintype "output"))
      (node (ref "IC7") (pin "30") (pinfunction "VINR3/VIN3P_30") (pintype "input"))
      (node (ref "R23") (pin "2") (pinfunction "2_2") (pintype "passive"))
    )
    (net (code "49") (name "Net-(IC4B--IN)") (class "Default")
      (node (ref "IC4") (pin "6") (pinfunction "-IN_6") (pintype "input"))
      (node (ref "R16") (pin "2") (pinfunction "2_2") (pintype "passive"))
      (node (ref "R24") (pin "1") (pinfunction "1_1") (pintype "passive"))
    )
    (net (code "50") (name "Net-(IC4B-OUT)") (class "Default")
      (node (ref "IC4") (pin "7") (pinfunction "OUT_7") (pintype "output"))
      (node (ref "IC7") (pin "29") (pinfunction "VINL3/VIN4P_29") (pintype "input"))
      (node (ref "R24") (pin "2") (pinfunction "2_2") (pintype "passive"))
    )
    (net (code "51") (name "Net-(IC6-LDO)") (class "Default")
      (node (ref "C27") (pin "1") (pinfunction "1_1") (pintype "passive"))
      (node (ref "C29") (pin "1") (pinfunction "1_1") (pintype "passive"))
      (node (ref "IC6") (pin "11") (pinfunction "LDO_11") (pintype "bidirectional"))
    )
    (net (code "52") (name "Net-(IC6-VREF)") (class "Default")
      (node (ref "C20") (pin "1") (pinfunction "1_1") (pintype "passive"))
      (node (ref "IC6") (pin "6") (pinfunction "VREF_6") (pintype "output"))
      (node (ref "R25") (pin "1") (pinfunction "1_1") (pintype "passive"))
    )
    (net (code "53") (name "Net-(IC7-LDO)") (class "Default")
      (node (ref "C28") (pin "1") (pinfunction "1_1") (pintype "passive"))
      (node (ref "C30") (pin "1") (pinfunction "1_1") (pintype "passive"))
      (node (ref "IC7") (pin "11") (pinfunction "LDO_11") (pintype "bidirectional"))
    )
    (net (code "54") (name "Net-(IC7-VREF)") (class "Default")
      (node (ref "C21") (pin "1") (pinfunction "1_1") (pintype "passive"))
      (node (ref "IC7") (pin "6") (pinfunction "VREF_6") (pintype "output"))
      (node (ref "R26") (pin "1") (pinfunction "1_1") (pintype "passive"))
    )
    (net (code "55") (name "Net-(IN1A-K)") (class "Default")
      (node (ref "C4") (pin "1") (pinfunction "1_1") (pintype "passive"))
      (node (ref "IN1") (pin "1") (pinfunction "K_1") (pintype "passive"))
      (node (ref "R4") (pin "1") (pinfunction "1_1") (pintype "passive"))
    )
    (net (code "56") (name "Net-(IN1B-K)") (class "Default")
      (node (ref "C3") (pin "1") (pinfunction "1_1") (pintype "passive"))
      (node (ref "IN1") (pin "2") (pinfunction "K_2") (pintype "passive"))
      (node (ref "R3") (pin "1") (pinfunction "1_1") (pintype "passive"))
    )
    (net (code "57") (name "Net-(IN1C-K)") (class "Default")
      (node (ref "C2") (pin "1") (pinfunction "1_1") (pintype "passive"))
      (node (ref "IN1") (pin "3") (pinfunction "K_3") (pintype "passive"))
      (node (ref "R2") (pin "1") (pinfunction "1_1") (pintype "passive"))
    )
    (net (code "58") (name "Net-(IN1D-K)") (class "Default")
      (node (ref "C1") (pin "1") (pinfunction "1_1") (pintype "passive"))
      (node (ref "IN1") (pin "4") (pinfunction "K_4") (pintype "passive"))
      (node (ref "R1") (pin "1") (pinfunction "1_1") (pintype "passive"))
    )
    (net (code "59") (name "Net-(IN2A-K)") (class "Default")
      (node (ref "C8") (pin "1") (pinfunction "1_1") (pintype "passive"))
      (node (ref "IN2") (pin "1") (pinfunction "K_1") (pintype "passive"))
      (node (ref "R8") (pin "1") (pinfunction "1_1") (pintype "passive"))
    )
    (net (code "60") (name "Net-(IN2B-K)") (class "Default")
      (node (ref "C7") (pin "1") (pinfunction "1_1") (pintype "passive"))
      (node (ref "IN2") (pin "2") (pinfunction "K_2") (pintype "passive"))
      (node (ref "R7") (pin "1") (pinfunction "1_1") (pintype "passive"))
    )
    (net (code "61") (name "Net-(IN2C-K)") (class "Default")
      (node (ref "C6") (pin "1") (pinfunction "1_1") (pintype "passive"))
      (node (ref "IN2") (pin "3") (pinfunction "K_3") (pintype "passive"))
      (node (ref "R6") (pin "1") (pinfunction "1_1") (pintype "passive"))
    )
    (net (code "62") (name "Net-(IN2D-K)") (class "Default")
      (node (ref "C5") (pin "1") (pinfunction "1_1") (pintype "passive"))
      (node (ref "IN2") (pin "4") (pinfunction "K_4") (pintype "passive"))
      (node (ref "R5") (pin "1") (pinfunction "1_1") (pintype "passive"))
    )
    (net (code "63") (name "Net-(LED1-PadA)") (class "Default")
      (node (ref "LED1") (pin "A") (pinfunction "A_A") (pintype "passive"))
      (node (ref "R32") (pin "1") (pinfunction "1_1") (pintype "passive"))
    )
    (net (code "64") (name "SCL") (class "Default")
      (node (ref "IC6") (pin "24") (pinfunction "MC/SCL_24") (pintype "input"))
      (node (ref "IC7") (pin "24") (pinfunction "MC/SCL_24") (pintype "input"))
      (node (ref "R27") (pin "1") (pinfunction "1_1") (pintype "passive"))
      (node (ref "TEENSY4.1") (pin "41") (pinfunction "19/A5/SCL_41") (pintype "bidirectional"))
    )
    (net (code "65") (name "SCL2") (class "Default")
      (node (ref "TEENSY4.1") (pin "38") (pinfunction "16/A2/RX4/SCL1_38") (pintype "bidirectional"))
    )
    (net (code "66") (name "SDA") (class "Default")
      (node (ref "IC6") (pin "23") (pinfunction "MOSI/SDA_23") (pintype "bidirectional"))
      (node (ref "IC7") (pin "23") (pinfunction "MOSI/SDA_23") (pintype "bidirectional"))
      (node (ref "R28") (pin "1") (pinfunction "1_1") (pintype "passive"))
      (node (ref "TEENSY4.1") (pin "40") (pinfunction "18/A4/SDA_40") (pintype "bidirectional"))
    )
    (net (code "67") (name "SDA2") (class "Default")
      (node (ref "TEENSY4.1") (pin "39") (pinfunction "17/A3/TX4/SDA1_39") (pintype "bidirectional"))
    )
    (net (code "68") (name "VDD") (class "Default")
      (node (ref "C31") (pin "1") (pinfunction "1_1") (pintype "passive"))
      (node (ref "C32") (pin "1") (pinfunction "1_1") (pintype "passive"))
      (node (ref "C33") (pin "1") (pinfunction "1_1") (pintype "passive"))
      (node (ref "C34") (pin "1") (pinfunction "1_1") (pintype "passive"))
      (node (ref "C37") (pin "1") (pinfunction "1_1") (pintype "passive"))
      (node (ref "C38") (pin "1") (pinfunction "1_1") (pintype "passive"))
      (node (ref "IC6") (pin "13") (pinfunction "DVDD_13") (pintype "power_in"))
      (node (ref "IC6") (pin "14") (pinfunction "IOVDD_14") (pintype "power_in"))
      (node (ref "IC7") (pin "13") (pinfunction "DVDD_13") (pintype "power_in"))
      (node (ref "IC7") (pin "14") (pinfunction "IOVDD_14") (pintype "power_in"))
      (node (ref "IC7") (pin "25") (pinfunction "MS/AD_25") (pintype "input"))
      (node (ref "IC8") (pin "3") (pinfunction "VCC_3") (pintype "power_in"))
      (node (ref "R27") (pin "2") (pinfunction "2_2") (pintype "passive"))
      (node (ref "R28") (pin "2") (pinfunction "2_2") (pintype "passive"))
      (node (ref "R32") (pin "2") (pinfunction "2_2") (pintype "passive"))
      (node (ref "TEENSY4.1") (pin "15") (pinfunction "3.3V_15") (pintype "output"))
      (node (ref "TEENSY4.1") (pin "46") (pinfunction "3.3V_46") (pintype "output"))
    )
    (net (code "69") (name "VDDA") (class "Default")
      (node (ref "C10") (pin "1") (pinfunction "1_1") (pintype "passive"))
      (node (ref "C11") (pin "1") (pinfunction "1_1") (pintype "passive"))
      (node (ref "C12") (pin "1") (pinfunction "1_1") (pintype "passive"))
      (node (ref "C17") (pin "1") (pinfunction "1_1") (pintype "passive"))
      (node (ref "C22") (pin "1") (pinfunction "1_1") (pintype "passive"))
      (node (ref "C23") (pin "1") (pinfunction "1_1") (pintype "passive"))
      (node (ref "C25") (pin "1") (pinfunction "1_1") (pintype "passive"))
      (node (ref "C26") (pin "1") (pinfunction "1_1") (pintype "passive"))
      (node (ref "C9") (pin "1") (pinfunction "1_1") (pintype "passive"))
      (node (ref "IC1") (pin "8") (pinfunction "V+_8") (pintype "power_in"))
      (node (ref "IC2") (pin "8") (pinfunction "V+_8") (pintype "power_in"))
      (node (ref "IC3") (pin "8") (pinfunction "V+_8") (pintype "power_in"))
      (node (ref "IC4") (pin "8") (pinfunction "V+_8") (pintype "power_in"))
      (node (ref "IC5") (pin "5") (pinfunction "OUT_5") (pintype "output"))
      (node (ref "IC6") (pin "8") (pinfunction "AVDD_8") (pintype "power_in"))
      (node (ref "IC7") (pin "8") (pinfunction "AVDD_8") (pintype "power_in"))
    )
    (net (code "70") (name "unconnected-(DN1-C4-Pad4)") (class "Default")
      (node (ref "DN1") (pin "4") (pinfunction "C4_4") (pintype "passive"))
    )
    (net (code "71") (name "unconnected-(IC6-GPIO1{slash}INTA{slash}DMIN-Pad21)") (class "Default")
      (node (ref "IC6") (pin "21") (pinfunction "GPIO1/INTA/DMIN_21") (pintype "bidirectional"))
    )
    (net (code "72") (name "unconnected-(IC6-GPIO2{slash}INTB{slash}DMCLK-Pad20)") (class "Default")
      (node (ref "IC6") (pin "20") (pinfunction "GPIO2/INTB/DMCLK_20") (pintype "bidirectional"))
    )
    (net (code "73") (name "unconnected-(IC6-MICBIAS-Pad5)") (class "Default")
      (node (ref "IC6") (pin "5") (pinfunction "MICBIAS_5") (pintype "input"))
    )
    (net (code "74") (name "unconnected-(IC6-MISO{slash}GPIO0{slash}DMIN2-Pad22)") (class "Default")
      (node (ref "IC6") (pin "22") (pinfunction "MISO/GPIO0/DMIN2_22") (pintype "bidirectional"))
    )
    (net (code "75") (name "unconnected-(IC6-SCKI-Pad15)") (class "Default")
      (node (ref "IC6") (pin "15") (pinfunction "SCKI_15") (pintype "input"))
    )
    (net (code "76") (name "unconnected-(IC6-VINL1{slash}VIN1P-Pad3)") (class "Default")
      (node (ref "IC6") (pin "3") (pinfunction "VINL1/VIN1P_3") (pintype "input"))
    )
    (net (code "77") (name "unconnected-(IC6-VINL4{slash}VIN4M-Pad27)") (class "Default")
      (node (ref "IC6") (pin "27") (pinfunction "VINL4/VIN4M_27") (pintype "input"))
    )
    (net (code "78") (name "unconnected-(IC6-VINR1{slash}VIN2P-Pad4)") (class "Default")
      (node (ref "IC6") (pin "4") (pinfunction "VINR1/VIN2P_4") (pintype "input"))
    )
    (net (code "79") (name "unconnected-(IC6-VINR4{slash}VIN3M-Pad28)") (class "Default")
      (node (ref "IC6") (pin "28") (pinfunction "VINR4/VIN3M_28") (pintype "input"))
    )
    (net (code "80") (name "unconnected-(IC6-XI-Pad10)") (class "Default")
      (node (ref "IC6") (pin "10") (pinfunction "XI_10") (pintype "input"))
    )
    (net (code "81") (name "unconnected-(IC6-XO-Pad9)") (class "Default")
      (node (ref "IC6") (pin "9") (pinfunction "XO_9") (pintype "output"))
    )
    (net (code "82") (name "unconnected-(IC7-GPIO1{slash}INTA{slash}DMIN-Pad21)") (class "Default")
      (node (ref "IC7") (pin "21") (pinfunction "GPIO1/INTA/DMIN_21") (pintype "bidirectional"))
    )
    (net (code "83") (name "unconnected-(IC7-GPIO2{slash}INTB{slash}DMCLK-Pad20)") (class "Default")
      (node (ref "IC7") (pin "20") (pinfunction "GPIO2/INTB/DMCLK_20") (pintype "bidirectional"))
    )
    (net (code "84") (name "unconnected-(IC7-MICBIAS-Pad5)") (class "Default")
      (node (ref "IC7") (pin "5") (pinfunction "MICBIAS_5") (pintype "input"))
    )
    (net (code "85") (name "unconnected-(IC7-MISO{slash}GPIO0{slash}DMIN2-Pad22)") (class "Default")
      (node (ref "IC7") (pin "22") (pinfunction "MISO/GPIO0/DMIN2_22") (pintype "bidirectional"))
    )
    (net (code "86") (name "unconnected-(IC7-SCKI-Pad15)") (class "Default")
      (node (ref "IC7") (pin "15") (pinfunction "SCKI_15") (pintype "input"))
    )
    (net (code "87") (name "unconnected-(IC7-VINL1{slash}VIN1P-Pad3)") (class "Default")
      (node (ref "IC7") (pin "3") (pinfunction "VINL1/VIN1P_3") (pintype "input"))
    )
    (net (code "88") (name "unconnected-(IC7-VINL4{slash}VIN4M-Pad27)") (class "Default")
      (node (ref "IC7") (pin "27") (pinfunction "VINL4/VIN4M_27") (pintype "input"))
    )
    (net (code "89") (name "unconnected-(IC7-VINR1{slash}VIN2P-Pad4)") (class "Default")
      (node (ref "IC7") (pin "4") (pinfunction "VINR1/VIN2P_4") (pintype "input"))
    )
    (net (code "90") (name "unconnected-(IC7-VINR4{slash}VIN3M-Pad28)") (class "Default")
      (node (ref "IC7") (pin "28") (pinfunction "VINR4/VIN3M_28") (pintype "input"))
    )
    (net (code "91") (name "unconnected-(IC7-XI-Pad10)") (class "Default")
      (node (ref "IC7") (pin "10") (pinfunction "XI_10") (pintype "input"))
    )
    (net (code "92") (name "unconnected-(IC7-XO-Pad9)") (class "Default")
      (node (ref "IC7") (pin "9") (pinfunction "XO_9") (pintype "output"))
    )
    (net (code "93") (name "unconnected-(TEENSY4.1-2{slash}OUT2-Pad4)") (class "Default")
      (node (ref "TEENSY4.1") (pin "4") (pinfunction "2/OUT2_4") (pintype "bidirectional"))
    )
    (net (code "94") (name "unconnected-(TEENSY4.1-6{slash}OUT1D-Pad8)") (class "Default")
      (node (ref "TEENSY4.1") (pin "8") (pinfunction "6/OUT1D_8") (pintype "bidirectional"))
    )
    (net (code "95") (name "unconnected-(TEENSY4.1-7{slash}RX2{slash}OUT1A-Pad9)") (class "Default")
      (node (ref "TEENSY4.1") (pin "9") (pinfunction "7/RX2/OUT1A_9") (pintype "bidirectional"))
    )
    (net (code "96") (name "unconnected-(TEENSY4.1-9{slash}OUT1C-Pad11)") (class "Default")
      (node (ref "TEENSY4.1") (pin "11") (pinfunction "9/OUT1C_11") (pintype "bidirectional"))
    )
    (net (code "97") (name "unconnected-(TEENSY4.1-10{slash}CS{slash}MOSR-Pad12)") (class "Default")
      (node (ref "TEENSY4.1") (pin "12") (pinfunction "10/CS/MOSR_12") (pintype "bidirectional"))
    )
    (net (code "98") (name "unconnected-(TEENSY4.1-11{slash}MOSI-Pad13)") (class "Default")
      (node (ref "TEENSY4.1") (pin "13") (pinfunction "11/MOSI_13") (pintype "bidirectional"))
    )
    (net (code "99") (name "unconnected-(TEENSY4.1-12{slash}MISO{slash}MQSL-Pad14)") (class "Default")
      (node (ref "TEENSY4.1") (pin "14") (pinfunction "12/MISO/MQSL_14") (pintype "bidirectional"))
    )
    (net (code "100") (name "unconnected-(TEENSY4.1-13(LED){slash}SCK-Pad35)") (class "Default")
      (node (ref "TEENSY4.1") (pin "35") (pinfunction "13(LED)/SCK_35") (pintype "bidirectional"))
    )
    (net (code "101") (name "unconnected-(TEENSY4.1-14{slash}A0{slash}TX3{slash}SPDIFOUT-Pad36)") (class "Default")
      (node (ref "TEENSY4.1") (pin "36") (pinfunction "14/A0/TX3/SPDIFOUT_36") (pintype "bidirectional"))
    )
    (net (code "102") (name "unconnected-(TEENSY4.1-23{slash}A9{slash}MCLK1-Pad45)") (class "Default")
      (node (ref "TEENSY4.1") (pin "45") (pinfunction "23/A9/MCLK1_45") (pintype "bidirectional"))
    )
    (net (code "103") (name "unconnected-(TEENSY4.1-24{slash}A10{slash}TX6{slash}SCL2-Pad16)") (class "Default")
      (node (ref "TEENSY4.1") (pin "16") (pinfunction "24/A10/TX6/SCL2_16") (pintype "bidirectional"))
    )
    (net (code "104") (name "unconnected-(TEENSY4.1-25{slash}A11{slash}RX6{slash}SDA2-Pad17)") (class "Default")
      (node (ref "TEENSY4.1") (pin "17") (pinfunction "25/A11/RX6/SDA2_17") (pintype "bidirectional"))
    )
    (net (code "105") (name "unconnected-(TEENSY4.1-27A13{slash}{slash}SCK1-Pad19)") (class "Default")
      (node (ref "TEENSY4.1") (pin "19") (pinfunction "27A13//SCK1_19") (pintype "bidirectional"))
    )
    (net (code "106") (name "unconnected-(TEENSY4.1-28{slash}RX7-Pad20)") (class "Default")
      (node (ref "TEENSY4.1") (pin "20") (pinfunction "28/RX7_20") (pintype "bidirectional"))
    )
    (net (code "107") (name "unconnected-(TEENSY4.1-29{slash}TX7-Pad21)") (class "Default")
      (node (ref "TEENSY4.1") (pin "21") (pinfunction "29/TX7_21") (pintype "bidirectional"))
    )
    (net (code "108") (name "unconnected-(TEENSY4.1-32{slash}OUT1B-Pad24)") (class "Default")
      (node (ref "TEENSY4.1") (pin "24") (pinfunction "32/OUT1B_24") (pintype "bidirectional"))
    )
    (net (code "109") (name "unconnected-(TEENSY4.1-33{slash}MCLK2-Pad25)") (class "Default")
      (node (ref "TEENSY4.1") (pin "25") (pinfunction "33/MCLK2_25") (pintype "bidirectional"))
    )
    (net (code "110") (name "unconnected-(TEENSY4.1-34{slash}RX8-Pad26)") (class "Default")
      (node (ref "TEENSY4.1") (pin "26") (pinfunction "34/RX8_26") (pintype "bidirectional"))
    )
    (net (code "111") (name "unconnected-(TEENSY4.1-35{slash}TX8-Pad27)") (class "Default")
      (node (ref "TEENSY4.1") (pin "27") (pinfunction "35/TX8_27") (pintype "bidirectional"))
    )
    (net (code "112") (name "unconnected-(TEENSY4.1-38{slash}A15{slash}CS1{slash}IN1-Pad30)") (class "Default")
      (node (ref "TEENSY4.1") (pin "30") (pinfunction "38/A15/CS1/IN1_30") (pintype "bidirectional"))
    )
    (net (code "113") (name "unconnected-(TEENSY4.1-39{slash}A15{slash}MISO1{slash}OUT1A-Pad31)") (class "Default")
      (node (ref "TEENSY4.1") (pin "31") (pinfunction "39/A15/MISO1/OUT1A_31") (pintype "bidirectional"))
    )
  )
)
